# STM32.net
KiCad netlist of a schematic drawn in Altium Designer
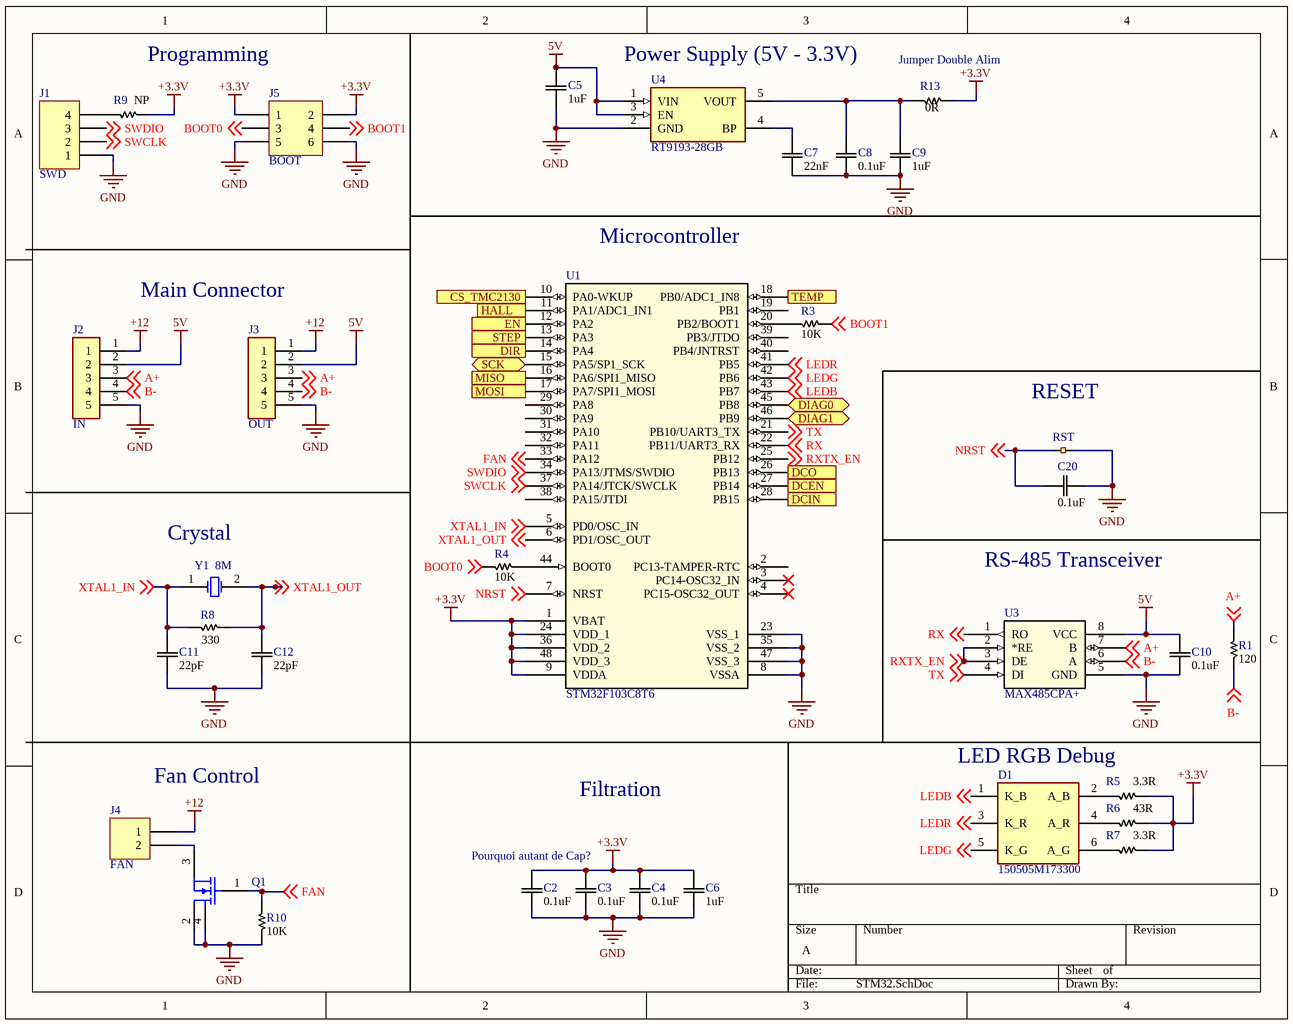
[diagram p0: STM32.SchDoc]

(export (version "E")
  (design (tool "Eeschema 10.0.6"))
  (components
    (comp (ref "C2")
      (value "0.1uF")
      (footprint "0603")
      (description "Capacitor SMD 1206")
      (fields
        (field (name "MANUFACTURER_PART_NUMBER") "12065A820JAT2A")
        (field (name "Comment") "Capacitor 1206")
        (field (name "COPYRIGHT") "Copyright (C) 2018 Accelerated Designs. All rights reserved")
      )
      (libsource (lib "Schematic_Emile") (part "Capacitor 1206"))
    )
    (comp (ref "C3")
      (value "0.1uF")
      (footprint "0603")
      (description "Capacitor SMD 1206")
      (fields
        (field (name "MANUFACTURER_PART_NUMBER") "12065A820JAT2A")
        (field (name "Comment") "Capacitor 1206")
        (field (name "COPYRIGHT") "Copyright (C) 2018 Accelerated Designs. All rights reserved")
      )
      (libsource (lib "Schematic_Emile") (part "Capacitor 1206"))
    )
    (comp (ref "C4")
      (value "0.1uF")
      (footprint "0603")
      (description "Capacitor SMD 1206")
      (fields
        (field (name "MANUFACTURER_PART_NUMBER") "12065A820JAT2A")
        (field (name "Comment") "Capacitor 1206")
        (field (name "COPYRIGHT") "Copyright (C) 2018 Accelerated Designs. All rights reserved")
      )
      (libsource (lib "Schematic_Emile") (part "Capacitor 1206"))
    )
    (comp (ref "C5")
      (value "1uF")
      (footprint "0603")
      (description "Capacitor SMD 1206")
      (fields
        (field (name "MANUFACTURER_PART_NUMBER") "12065A820JAT2A")
        (field (name "Comment") "Capacitor 1206")
        (field (name "COPYRIGHT") "Copyright (C) 2018 Accelerated Designs. All rights reserved")
      )
      (libsource (lib "Schematic_Emile") (part "Capacitor 1206"))
    )
    (comp (ref "C6")
      (value "1uF")
      (footprint "0603")
      (description "Capacitor SMD 1206")
      (fields
        (field (name "MANUFACTURER_PART_NUMBER") "12065A820JAT2A")
        (field (name "Comment") "Capacitor 1206")
        (field (name "COPYRIGHT") "Copyright (C) 2018 Accelerated Designs. All rights reserved")
      )
      (libsource (lib "Schematic_Emile") (part "Capacitor 1206"))
    )
    (comp (ref "C7")
      (value "22nF")
      (footprint "0603")
      (description "Capacitor SMD 1206")
      (fields
        (field (name "MANUFACTURER_PART_NUMBER") "12065A820JAT2A")
        (field (name "Comment") "Capacitor 1206")
        (field (name "COPYRIGHT") "Copyright (C) 2018 Accelerated Designs. All rights reserved")
      )
      (libsource (lib "Schematic_Emile") (part "Capacitor 1206"))
    )
    (comp (ref "C8")
      (value "0.1uF")
      (footprint "0603")
      (description "Capacitor SMD 1206")
      (fields
        (field (name "MANUFACTURER_PART_NUMBER") "12065A820JAT2A")
        (field (name "Comment") "Capacitor 1206")
        (field (name "COPYRIGHT") "Copyright (C) 2018 Accelerated Designs. All rights reserved")
      )
      (libsource (lib "Schematic_Emile") (part "Capacitor 1206"))
    )
    (comp (ref "C9")
      (value "1uF")
      (footprint "0603")
      (description "Capacitor SMD 1206")
      (fields
        (field (name "MANUFACTURER_PART_NUMBER") "12065A820JAT2A")
        (field (name "Comment") "Capacitor 1206")
        (field (name "COPYRIGHT") "Copyright (C) 2018 Accelerated Designs. All rights reserved")
      )
      (libsource (lib "Schematic_Emile") (part "Capacitor 1206"))
    )
    (comp (ref "C10")
      (value "0.1uF")
      (footprint "0603")
      (description "Capacitor SMD 1206")
      (fields
        (field (name "MANUFACTURER_PART_NUMBER") "12065A820JAT2A")
        (field (name "Comment") "Capacitor 1206")
        (field (name "COPYRIGHT") "Copyright (C) 2018 Accelerated Designs. All rights reserved")
      )
      (libsource (lib "Schematic_Emile") (part "Capacitor 1206"))
    )
    (comp (ref "C11")
      (value "22pF")
      (footprint "0603")
      (description "Capacitor SMD 1206")
      (fields
        (field (name "MANUFACTURER_PART_NUMBER") "12065A820JAT2A")
        (field (name "Comment") "Capacitor 1206")
        (field (name "COPYRIGHT") "Copyright (C) 2018 Accelerated Designs. All rights reserved")
      )
      (libsource (lib "Schematic_Emile") (part "Capacitor 1206"))
    )
    (comp (ref "C12")
      (value "22pF")
      (footprint "0603")
      (description "Capacitor SMD 1206")
      (fields
        (field (name "MANUFACTURER_PART_NUMBER") "12065A820JAT2A")
        (field (name "Comment") "Capacitor 1206")
        (field (name "COPYRIGHT") "Copyright (C) 2018 Accelerated Designs. All rights reserved")
      )
      (libsource (lib "Schematic_Emile") (part "Capacitor 1206"))
    )
    (comp (ref "C20")
      (value "0.1uF")
      (footprint "0603")
      (description "Capacitor SMD 1206")
      (fields
        (field (name "MANUFACTURER_PART_NUMBER") "12065A820JAT2A")
        (field (name "Comment") "Capacitor 1206")
        (field (name "COPYRIGHT") "Copyright (C) 2018 Accelerated Designs. All rights reserved")
      )
      (libsource (lib "Schematic_Emile") (part "Capacitor 1206"))
    )
    (comp (ref "D1")
      (value "150505M173300")
      (footprint "LED 5050")
      (description "LED")
      (fields
        (field (name "MOUSER PART NUMBER") "710-150505M173300")
        (field (name "RS PART NUMBER") "1766248P")
      )
      (libsource (lib "Schematic_Emile") (part "150505M173300"))
    )
    (comp (ref "J1")
      (value "SWD")
      (footprint "HDR1X4")
      (description "Header, 4-Pin")
      (fields (field (name "PUBLISHER") "Altium Limited"))
      (libsource (lib "Miscellaneous Connectors") (part "Header 4"))
    )
    (comp (ref "J2")
      (value "IN")
      (footprint "JST 5POS 2.5mm 90°")
      (description "Connector")
      (fields (field (name "MANUFACTURER_PART_NUMBER") "S5B-XH-A-1(LF)(SN)"))
      (libsource (lib "Schematic_Emile") (part "JST 5POS"))
    )
    (comp (ref "J3")
      (value "OUT")
      (footprint "JST 5POS 2.5mm 90°")
      (description "Connector")
      (fields (field (name "MANUFACTURER_PART_NUMBER") "S5B-XH-A-1(LF)(SN)"))
      (libsource (lib "Schematic_Emile") (part "JST 5POS"))
    )
    (comp (ref "J4")
      (value "FAN")
      (footprint "HDR1X2")
      (description "Header, 2-Pin")
      (fields (field (name "PUBLISHER") "Altium Limited"))
      (libsource (lib "Miscellaneous Connectors") (part "Header 2"))
    )
    (comp (ref "J5")
      (value "BOOT")
      (footprint "Header 3x2 1.27mm SMD")
      (description "Header, 3-Pin, Dual row")
      (fields (field (name "PUBLISHER") "Altium Limited"))
      (libsource (lib "Miscellaneous Connectors") (part "Header 3X2"))
    )
    (comp (ref "Q1")
      (value "MOSFET N-CH")
      (footprint "SOT223_M")
      (description "55V 7A SOT223")
      (libsource (lib "Schematic_Emile") (part "MOSFET N-CH"))
    )
    (comp (ref "R1")
      (value "120")
      (footprint "0603")
      (description "Resistor 0603 SMD")
      (fields
        (field (name "MANUFACTURER_PART_NUMBER") "ERJ8CWFR024V")
        (field (name "Comment") "Resistor 0603")
        (field (name "COPYRIGHT") "Copyright (C) 2018 Accelerated Designs. All rights reserved")
      )
      (libsource (lib "Schematic_Emile") (part "Resistor 1206"))
    )
    (comp (ref "R3")
      (value "10K")
      (footprint "0603")
      (description "Resistor 1206 SMD")
      (fields
        (field (name "MANUFACTURER_PART_NUMBER") "ERJ8CWFR024V")
        (field (name "Comment") "Resistor 1206")
        (field (name "COPYRIGHT") "Copyright (C) 2018 Accelerated Designs. All rights reserved")
      )
      (libsource (lib "Schematic_Emile") (part "Resistor 1206"))
    )
    (comp (ref "R4")
      (value "10K")
      (footprint "0603")
      (description "Resistor 1206 SMD")
      (fields
        (field (name "MANUFACTURER_PART_NUMBER") "ERJ8CWFR024V")
        (field (name "Comment") "Resistor 1206")
        (field (name "COPYRIGHT") "Copyright (C) 2018 Accelerated Designs. All rights reserved")
      )
      (libsource (lib "Schematic_Emile") (part "Resistor 1206"))
    )
    (comp (ref "R5")
      (value "3.3R")
      (footprint "0603")
      (description "Resistor 0603 SMD")
      (fields
        (field (name "MANUFACTURER_PART_NUMBER") "ERJ8CWFR024V")
        (field (name "Comment") "Resistor 0603")
        (field (name "COPYRIGHT") "Copyright (C) 2018 Accelerated Designs. All rights reserved")
      )
      (libsource (lib "Schematic_Emile") (part "Resistor 1206"))
    )
    (comp (ref "R6")
      (value "43R")
      (footprint "0603")
      (description "Resistor 0603 SMD")
      (fields
        (field (name "MANUFACTURER_PART_NUMBER") "ERJ8CWFR024V")
        (field (name "Comment") "Resistor 0603")
        (field (name "COPYRIGHT") "Copyright (C) 2018 Accelerated Designs. All rights reserved")
      )
      (libsource (lib "Schematic_Emile") (part "Resistor 1206"))
    )
    (comp (ref "R7")
      (value "3.3R")
      (footprint "0603")
      (description "Resistor 0603 SMD")
      (fields
        (field (name "MANUFACTURER_PART_NUMBER") "ERJ8CWFR024V")
        (field (name "Comment") "Resistor 0603")
        (field (name "COPYRIGHT") "Copyright (C) 2018 Accelerated Designs. All rights reserved")
      )
      (libsource (lib "Schematic_Emile") (part "Resistor 1206"))
    )
    (comp (ref "R8")
      (value "330")
      (footprint "0603")
      (description "Resistor 0603 SMD")
      (fields
        (field (name "MANUFACTURER_PART_NUMBER") "ERJ8CWFR024V")
        (field (name "Comment") "Resistor 0603")
        (field (name "COPYRIGHT") "Copyright (C) 2018 Accelerated Designs. All rights reserved")
      )
      (libsource (lib "Schematic_Emile") (part "Resistor 1206"))
    )
    (comp (ref "R9")
      (value "NP")
      (footprint "0603")
      (description "Resistor 1206 SMD")
      (fields
        (field (name "MANUFACTURER_PART_NUMBER") "ERJ8CWFR024V")
        (field (name "Comment") "Jumper 0603")
        (field (name "COPYRIGHT") "Copyright (C) 2018 Accelerated Designs. All rights reserved")
      )
      (libsource (lib "Schematic_Emile") (part "Resistor 1206"))
    )
    (comp (ref "R10")
      (value "10K")
      (footprint "0603")
      (description "Resistor 0603 SMD")
      (fields
        (field (name "MANUFACTURER_PART_NUMBER") "ERJ8CWFR024V")
        (field (name "Comment") "Resistor 0603")
        (field (name "COPYRIGHT") "Copyright (C) 2018 Accelerated Designs. All rights reserved")
      )
      (libsource (lib "Schematic_Emile") (part "Resistor 1206"))
    )
    (comp (ref "R13")
      (value "0R")
      (footprint "0603")
      (description "Resistor 1206 SMD")
      (fields
        (field (name "MANUFACTURER_PART_NUMBER") "ERJ8CWFR024V")
        (field (name "Comment") "Jumper 0603")
        (field (name "COPYRIGHT") "Copyright (C) 2018 Accelerated Designs. All rights reserved")
      )
      (libsource (lib "Schematic_Emile") (part "Resistor 1206"))
    )
    (comp (ref "RST")
      (value "PAD")
      (footprint "PAD")
      (description "SMD Pad for contact")
      (libsource (lib "Schematic_Emile") (part "PAD"))
    )
    (comp (ref "U1")
      (value "STM32F103C8T6")
      (footprint "LQFP-48")
      (description "Integrated Circuit STM32")
      (fields (field (name "COPYRIGHT") "Copyright (C) 2018 Accelerated Designs. All rights reserved"))
      (libsource (lib "Schematic_Emile") (part "STM32F103C8T6"))
    )
    (comp (ref "U3")
      (value "MAX485CPA+")
      (footprint "DIP 8 - 3D")
      (description "RS485 Communication")
      (fields (field (name "COPYRIGHT") "Copyright (C) 2018 Accelerated Designs. All rights reserved"))
      (libsource (lib "Schematic_Emile") (part "MAX485CPA+"))
    )
    (comp (ref "U4")
      (value "RT9193-28GB")
      (footprint "SamacSys:SOT94P279X130-5N")
      (description "Voltage Regulator 3.3V")
      (libsource (lib "Schematic_Emile") (part "RT9193-28GB"))
    )
    (comp (ref "Y1")
      (value "8M")
      (footprint "ATS080B-E")
      (description "Crystal Oscillator")
      (fields (field (name "PUBLISHER") "Altium Limited"))
      (libsource (lib "Miscellaneous Devices") (part "XTAL"))
    )
  )
  (nets
    (net (code "1") (name "+3.3V") (class "Default")
      (node (ref "C2") (pin "2") (pinfunction "2_2") (pintype "passive"))
      (node (ref "C3") (pin "2") (pinfunction "2_2") (pintype "passive"))
      (node (ref "C4") (pin "2") (pinfunction "2_2") (pintype "passive"))
      (node (ref "C6") (pin "2") (pinfunction "2_2") (pintype "passive"))
      (node (ref "J5") (pin "1") (pinfunction "1_1") (pintype "passive"))
      (node (ref "J5") (pin "2") (pinfunction "2_2") (pintype "passive"))
      (node (ref "R13") (pin "2") (pinfunction "2_2") (pintype "passive"))
      (node (ref "R5") (pin "2") (pinfunction "2_2") (pintype "passive"))
      (node (ref "R6") (pin "2") (pinfunction "2_2") (pintype "passive"))
      (node (ref "R7") (pin "2") (pinfunction "2_2") (pintype "passive"))
      (node (ref "R9") (pin "2") (pinfunction "2_2") (pintype "passive"))
      (node (ref "U1") (pin "1") (pinfunction "VBAT_1") (pintype "power_in"))
      (node (ref "U1") (pin "24") (pinfunction "VDD_1_24") (pintype "power_in"))
      (node (ref "U1") (pin "36") (pinfunction "VDD_2_36") (pintype "power_in"))
      (node (ref "U1") (pin "48") (pinfunction "VDD_3_48") (pintype "power_in"))
      (node (ref "U1") (pin "9") (pinfunction "VDDA_9") (pintype "power_in"))
    )
    (net (code "2") (name "+12") (class "Default")
      (node (ref "J2") (pin "1") (pinfunction "1_1") (pintype "passive"))
      (node (ref "J3") (pin "1") (pinfunction "1_1") (pintype "passive"))
      (node (ref "J4") (pin "1") (pinfunction "1_1") (pintype "passive"))
    )
    (net (code "3") (name "/CS_TMC2130") (class "Default")
      (node (ref "U1") (pin "10") (pinfunction "PA0-WKUP_10") (pintype "bidirectional"))
    )
    (net (code "4") (name "/DCEN") (class "Default")
      (node (ref "U1") (pin "27") (pinfunction "PB14_27") (pintype "bidirectional"))
    )
    (net (code "5") (name "/DCIN") (class "Default")
      (node (ref "U1") (pin "28") (pinfunction "PB15_28") (pintype "bidirectional"))
    )
    (net (code "6") (name "/DCO") (class "Default")
      (node (ref "U1") (pin "26") (pinfunction "PB13_26") (pintype "bidirectional"))
    )
    (net (code "7") (name "/DIAG0") (class "Default")
      (node (ref "U1") (pin "45") (pinfunction "PB8_45") (pintype "bidirectional"))
    )
    (net (code "8") (name "/DIAG1") (class "Default")
      (node (ref "U1") (pin "46") (pinfunction "PB9_46") (pintype "bidirectional"))
    )
    (net (code "9") (name "/DIR") (class "Default")
      (node (ref "U1") (pin "14") (pinfunction "PA4_14") (pintype "bidirectional"))
    )
    (net (code "10") (name "/EN") (class "Default")
      (node (ref "U1") (pin "12") (pinfunction "PA2_12") (pintype "bidirectional"))
    )
    (net (code "11") (name "/HALL") (class "Default")
      (node (ref "U1") (pin "11") (pinfunction "PA1/ADC1_IN1_11") (pintype "bidirectional"))
    )
    (net (code "12") (name "/MISO") (class "Default")
      (node (ref "U1") (pin "16") (pinfunction "PA6/SPI1_MISO_16") (pintype "bidirectional"))
    )
    (net (code "13") (name "/MOSI") (class "Default")
      (node (ref "U1") (pin "17") (pinfunction "PA7/SPI1_MOSI_17") (pintype "bidirectional"))
    )
    (net (code "14") (name "/SCK") (class "Default")
      (node (ref "U1") (pin "15") (pinfunction "PA5/SP1_SCK_15") (pintype "bidirectional"))
    )
    (net (code "15") (name "/STEP") (class "Default")
      (node (ref "U1") (pin "13") (pinfunction "PA3_13") (pintype "bidirectional"))
    )
    (net (code "16") (name "/TEMP") (class "Default")
      (node (ref "U1") (pin "18") (pinfunction "PB0/ADC1_IN8_18") (pintype "bidirectional"))
    )
    (net (code "17") (name "5V") (class "Default")
      (node (ref "C10") (pin "2") (pinfunction "2_2") (pintype "passive"))
      (node (ref "C5") (pin "2") (pinfunction "2_2") (pintype "passive"))
      (node (ref "J2") (pin "2") (pinfunction "2_2") (pintype "passive"))
      (node (ref "J3") (pin "2") (pinfunction "2_2") (pintype "passive"))
      (node (ref "U3") (pin "8") (pinfunction "VCC_8") (pintype "power_in"))
      (node (ref "U4") (pin "1") (pinfunction "VIN_1") (pintype "input"))
      (node (ref "U4") (pin "3") (pinfunction "EN_3") (pintype "input"))
    )
    (net (code "18") (name "A+") (class "Default")
      (node (ref "J2") (pin "3") (pinfunction "3_3") (pintype "passive"))
      (node (ref "J3") (pin "3") (pinfunction "3_3") (pintype "passive"))
      (node (ref "R1") (pin "2") (pinfunction "2_2") (pintype "passive"))
      (node (ref "U3") (pin "7") (pinfunction "B_7") (pintype "bidirectional"))
    )
    (net (code "19") (name "B-") (class "Default")
      (node (ref "J2") (pin "4") (pinfunction "4_4") (pintype "passive"))
      (node (ref "J3") (pin "4") (pinfunction "4_4") (pintype "passive"))
      (node (ref "R1") (pin "1") (pinfunction "1_1") (pintype "passive"))
      (node (ref "U3") (pin "6") (pinfunction "A_6") (pintype "bidirectional"))
    )
    (net (code "20") (name "BOOT0") (class "Default")
      (node (ref "J5") (pin "3") (pinfunction "3_3") (pintype "passive"))
      (node (ref "R4") (pin "1") (pinfunction "1_1") (pintype "passive"))
    )
    (net (code "21") (name "BOOT1") (class "Default")
      (node (ref "J5") (pin "4") (pinfunction "4_4") (pintype "passive"))
      (node (ref "R3") (pin "2") (pinfunction "2_2") (pintype "passive"))
    )
    (net (code "22") (name "FAN") (class "Default")
      (node (ref "Q1") (pin "1") (pinfunction "G_1") (pintype "passive"))
      (node (ref "R10") (pin "2") (pinfunction "2_2") (pintype "passive"))
      (node (ref "U1") (pin "33") (pinfunction "PA12_33") (pintype "bidirectional"))
    )
    (net (code "23") (name "GND") (class "Default")
      (node (ref "C10") (pin "1") (pinfunction "1_1") (pintype "passive"))
      (node (ref "C11") (pin "1") (pinfunction "1_1") (pintype "passive"))
      (node (ref "C12") (pin "1") (pinfunction "1_1") (pintype "passive"))
      (node (ref "C2") (pin "1") (pinfunction "1_1") (pintype "passive"))
      (node (ref "C20") (pin "1") (pinfunction "1_1") (pintype "passive"))
      (node (ref "C3") (pin "1") (pinfunction "1_1") (pintype "passive"))
      (node (ref "C4") (pin "1") (pinfunction "1_1") (pintype "passive"))
      (node (ref "C5") (pin "1") (pinfunction "1_1") (pintype "passive"))
      (node (ref "C6") (pin "1") (pinfunction "1_1") (pintype "passive"))
      (node (ref "C7") (pin "1") (pinfunction "1_1") (pintype "passive"))
      (node (ref "C8") (pin "1") (pinfunction "1_1") (pintype "passive"))
      (node (ref "C9") (pin "1") (pinfunction "1_1") (pintype "passive"))
      (node (ref "J1") (pin "1") (pinfunction "1_1") (pintype "passive"))
      (node (ref "J2") (pin "5") (pinfunction "5_5") (pintype "passive"))
      (node (ref "J3") (pin "5") (pinfunction "5_5") (pintype "passive"))
      (node (ref "J5") (pin "5") (pinfunction "5_5") (pintype "passive"))
      (node (ref "J5") (pin "6") (pinfunction "6_6") (pintype "passive"))
      (node (ref "Q1") (pin "2") (pinfunction "D_2") (pintype "passive"))
      (node (ref "Q1") (pin "4") (pinfunction "D_4") (pintype "passive"))
      (node (ref "R10") (pin "1") (pinfunction "1_1") (pintype "passive"))
      (node (ref "RST") (pin "1") (pinfunction "1_1") (pintype "passive"))
      (node (ref "U1") (pin "23") (pinfunction "VSS_1_23") (pintype "power_in"))
      (node (ref "U1") (pin "35") (pinfunction "VSS_2_35") (pintype "power_in"))
      (node (ref "U1") (pin "47") (pinfunction "VSS_3_47") (pintype "power_in"))
      (node (ref "U1") (pin "8") (pinfunction "VSSA_8") (pintype "power_in"))
      (node (ref "U3") (pin "5") (pinfunction "GND_5") (pintype "power_in"))
      (node (ref "U4") (pin "2") (pinfunction "GND_2") (pintype "power_in"))
    )
    (net (code "24") (name "LEDB") (class "Default")
      (node (ref "D1") (pin "1") (pinfunction "K_B_1") (pintype "passive"))
      (node (ref "U1") (pin "43") (pinfunction "PB7_43") (pintype "bidirectional"))
    )
    (net (code "25") (name "LEDG") (class "Default")
      (node (ref "D1") (pin "5") (pinfunction "K_G_5") (pintype "passive"))
      (node (ref "U1") (pin "42") (pinfunction "PB6_42") (pintype "bidirectional"))
    )
    (net (code "26") (name "LEDR") (class "Default")
      (node (ref "D1") (pin "3") (pinfunction "K_R_3") (pintype "passive"))
      (node (ref "U1") (pin "41") (pinfunction "PB5_41") (pintype "bidirectional"))
    )
    (net (code "27") (name "NRST") (class "Default")
      (node (ref "C20") (pin "2") (pinfunction "2_2") (pintype "passive"))
      (node (ref "RST") (pin "2") (pinfunction "2_2") (pintype "passive"))
      (node (ref "U1") (pin "7") (pinfunction "NRST_7") (pintype "bidirectional"))
    )
    (net (code "28") (name "Net-(D1-A_B)") (class "Default")
      (node (ref "D1") (pin "2") (pinfunction "A_B_2") (pintype "passive"))
      (node (ref "R5") (pin "1") (pinfunction "1_1") (pintype "passive"))
    )
    (net (code "29") (name "Net-(D1-A_G)") (class "Default")
      (node (ref "D1") (pin "6") (pinfunction "A_G_6") (pintype "passive"))
      (node (ref "R7") (pin "1") (pinfunction "1_1") (pintype "passive"))
    )
    (net (code "30") (name "Net-(D1-A_R)") (class "Default")
      (node (ref "D1") (pin "4") (pinfunction "A_R_4") (pintype "passive"))
      (node (ref "R6") (pin "1") (pinfunction "1_1") (pintype "passive"))
    )
    (net (code "31") (name "Net-(J1-Pad4)") (class "Default")
      (node (ref "J1") (pin "4") (pinfunction "4_4") (pintype "passive"))
      (node (ref "R9") (pin "1") (pinfunction "1_1") (pintype "passive"))
    )
    (net (code "32") (name "Net-(Q1-S)") (class "Default")
      (node (ref "J4") (pin "2") (pinfunction "2_2") (pintype "passive"))
      (node (ref "Q1") (pin "3") (pinfunction "S_3") (pintype "passive"))
    )
    (net (code "33") (name "Net-(U1-BOOT0)") (class "Default")
      (node (ref "R4") (pin "2") (pinfunction "2_2") (pintype "passive"))
      (node (ref "U1") (pin "44") (pinfunction "BOOT0_44") (pintype "input"))
    )
    (net (code "34") (name "Net-(U1-PB2{slash}BOOT1)") (class "Default")
      (node (ref "R3") (pin "1") (pinfunction "1_1") (pintype "passive"))
      (node (ref "U1") (pin "20") (pinfunction "PB2/BOOT1_20") (pintype "bidirectional"))
    )
    (net (code "35") (name "Net-(U4-BP)") (class "Default")
      (node (ref "C7") (pin "2") (pinfunction "2_2") (pintype "passive"))
      (node (ref "U4") (pin "4") (pinfunction "BP_4") (pintype "passive"))
    )
    (net (code "36") (name "Net-(U4-VOUT)") (class "Default")
      (node (ref "C8") (pin "2") (pinfunction "2_2") (pintype "passive"))
      (node (ref "C9") (pin "2") (pinfunction "2_2") (pintype "passive"))
      (node (ref "R13") (pin "1") (pinfunction "1_1") (pintype "passive"))
      (node (ref "U4") (pin "5") (pinfunction "VOUT_5") (pintype "passive"))
    )
    (net (code "37") (name "RX") (class "Default")
      (node (ref "U1") (pin "22") (pinfunction "PB11/UART3_RX_22") (pintype "bidirectional"))
      (node (ref "U3") (pin "1") (pinfunction "RO_1") (pintype "output"))
    )
    (net (code "38") (name "RXTX_EN") (class "Default")
      (node (ref "U1") (pin "25") (pinfunction "PB12_25") (pintype "bidirectional"))
      (node (ref "U3") (pin "2") (pinfunction "*RE_2") (pintype "input"))
      (node (ref "U3") (pin "3") (pinfunction "DE_3") (pintype "input"))
    )
    (net (code "39") (name "SWCLK") (class "Default")
      (node (ref "J1") (pin "2") (pinfunction "2_2") (pintype "passive"))
      (node (ref "U1") (pin "37") (pinfunction "PA14/JTCK/SWCLK_37") (pintype "bidirectional"))
    )
    (net (code "40") (name "SWDIO") (class "Default")
      (node (ref "J1") (pin "3") (pinfunction "3_3") (pintype "passive"))
      (node (ref "U1") (pin "34") (pinfunction "PA13/JTMS/SWDIO_34") (pintype "bidirectional"))
    )
    (net (code "41") (name "TX") (class "Default")
      (node (ref "U1") (pin "21") (pinfunction "PB10/UART3_TX_21") (pintype "bidirectional"))
      (node (ref "U3") (pin "4") (pinfunction "DI_4") (pintype "input"))
    )
    (net (code "42") (name "XTAL1_IN") (class "Default")
      (node (ref "C11") (pin "2") (pinfunction "2_2") (pintype "passive"))
      (node (ref "R8") (pin "1") (pinfunction "1_1") (pintype "passive"))
      (node (ref "U1") (pin "5") (pinfunction "PD0/OSC_IN_5") (pintype "bidirectional"))
      (node (ref "Y1") (pin "1") (pinfunction "OSC1_1") (pintype "passive"))
    )
    (net (code "43") (name "XTAL1_OUT") (class "Default")
      (node (ref "C12") (pin "2") (pinfunction "2_2") (pintype "passive"))
      (node (ref "R8") (pin "2") (pinfunction "2_2") (pintype "passive"))
      (node (ref "U1") (pin "6") (pinfunction "PD1/OSC_OUT_6") (pintype "bidirectional"))
      (node (ref "Y1") (pin "2") (pinfunction "OSC2_2") (pintype "passive"))
    )
    (net (code "44") (name "unconnected-(U1-PA8-Pad29)") (class "Default")
      (node (ref "U1") (pin "29") (pinfunction "PA8_29") (pintype "bidirectional"))
    )
    (net (code "45") (name "unconnected-(U1-PA9-Pad30)") (class "Default")
      (node (ref "U1") (pin "30") (pinfunction "PA9_30") (pintype "bidirectional"))
    )
    (net (code "46") (name "unconnected-(U1-PA10-Pad31)") (class "Default")
      (node (ref "U1") (pin "31") (pinfunction "PA10_31") (pintype "bidirectional"))
    )
    (net (code "47") (name "unconnected-(U1-PA11-Pad32)") (class "Default")
      (node (ref "U1") (pin "32") (pinfunction "PA11_32") (pintype "bidirectional"))
    )
    (net (code "48") (name "unconnected-(U1-PA15{slash}JTDI-Pad38)") (class "Default")
      (node (ref "U1") (pin "38") (pinfunction "PA15/JTDI_38") (pintype "bidirectional"))
    )
    (net (code "49") (name "unconnected-(U1-PB1-Pad19)") (class "Default")
      (node (ref "U1") (pin "19") (pinfunction "PB1_19") (pintype "bidirectional"))
    )
    (net (code "50") (name "unconnected-(U1-PB3{slash}JTDO-Pad39)") (class "Default")
      (node (ref "U1") (pin "39") (pinfunction "PB3/JTDO_39") (pintype "bidirectional"))
    )
    (net (code "51") (name "unconnected-(U1-PB4{slash}JNTRST-Pad40)") (class "Default")
      (node (ref "U1") (pin "40") (pinfunction "PB4/JNTRST_40") (pintype "bidirectional"))
    )
    (net (code "52") (name "unconnected-(U1-PC13-TAMPER-RTC-Pad2)") (class "Default")
      (node (ref "U1") (pin "2") (pinfunction "PC13-TAMPER-RTC_2") (pintype "bidirectional"))
    )
    (net (code "53") (name "unconnected-(U1-PC14-OSC32_IN-Pad3)") (class "Default")
      (node (ref "U1") (pin "3") (pinfunction "PC14-OSC32_IN_3") (pintype "bidirectional+no_connect"))
    )
    (net (code "54") (name "unconnected-(U1-PC15-OSC32_OUT-Pad4)") (class "Default")
      (node (ref "U1") (pin "4") (pinfunction "PC15-OSC32_OUT_4") (pintype "bidirectional+no_connect"))
    )
  )
)
